# M8830C.net
KiCad netlist of a schematic drawn in EAGLE
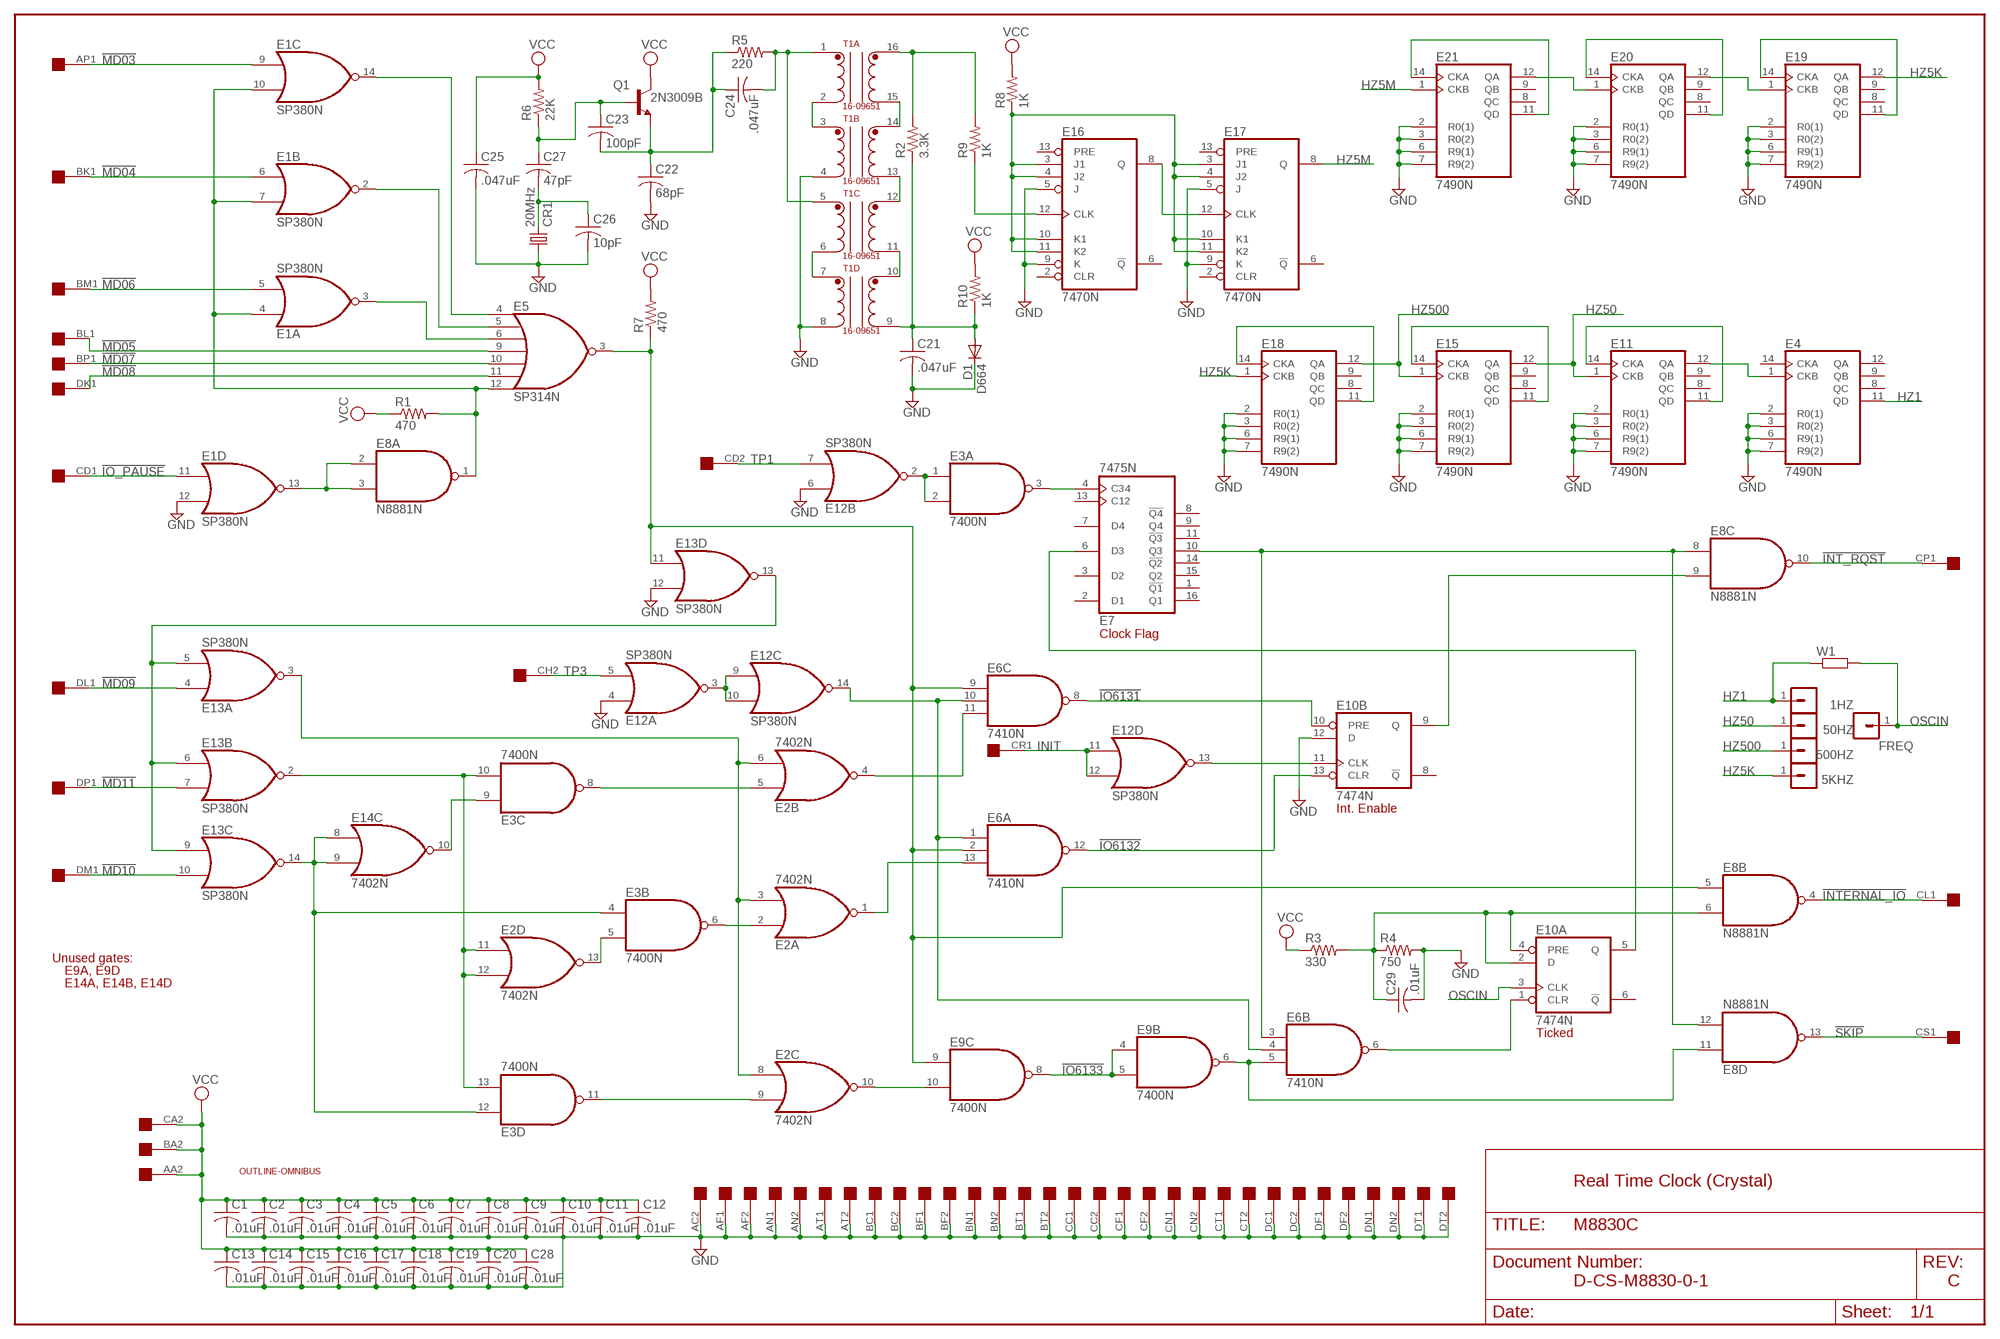
[diagram p0: schematic, sheet 1]

(export (version "E")
  (design (tool "Eeschema 10.0.6"))
  (components
    (comp (ref "1HZ")
      (value "MA01-1")
      (footprint "eagle-import:MA01-1")
      (libsource (lib "eagle-import") (part "MA01-1"))
    )
    (comp (ref "5KHZ")
      (value "MA01-1")
      (footprint "eagle-import:MA01-1")
      (libsource (lib "eagle-import") (part "MA01-1"))
    )
    (comp (ref "50HZ")
      (value "MA01-1")
      (footprint "eagle-import:MA01-1")
      (libsource (lib "eagle-import") (part "MA01-1"))
    )
    (comp (ref "500HZ")
      (value "MA01-1")
      (footprint "eagle-import:MA01-1")
      (libsource (lib "eagle-import") (part "MA01-1"))
    )
    (comp (ref "C1")
      (value ".01uF")
      (footprint "eagle-import:C050-025X075")
      (libsource (lib "eagle-import") (part "C-US050-025X075"))
    )
    (comp (ref "C2")
      (value ".01uF")
      (footprint "eagle-import:C050-025X075")
      (libsource (lib "eagle-import") (part "C-US050-025X075"))
    )
    (comp (ref "C3")
      (value ".01uF")
      (footprint "eagle-import:C050-025X075")
      (libsource (lib "eagle-import") (part "C-US050-025X075"))
    )
    (comp (ref "C4")
      (value ".01uF")
      (footprint "eagle-import:C050-025X075")
      (libsource (lib "eagle-import") (part "C-US050-025X075"))
    )
    (comp (ref "C5")
      (value ".01uF")
      (footprint "eagle-import:C050-025X075")
      (libsource (lib "eagle-import") (part "C-US050-025X075"))
    )
    (comp (ref "C6")
      (value ".01uF")
      (footprint "eagle-import:C050-025X075")
      (libsource (lib "eagle-import") (part "C-US050-025X075"))
    )
    (comp (ref "C7")
      (value ".01uF")
      (footprint "eagle-import:C050-025X075")
      (libsource (lib "eagle-import") (part "C-US050-025X075"))
    )
    (comp (ref "C8")
      (value ".01uF")
      (footprint "eagle-import:C050-025X075")
      (libsource (lib "eagle-import") (part "C-US050-025X075"))
    )
    (comp (ref "C9")
      (value ".01uF")
      (footprint "eagle-import:C050-025X075")
      (libsource (lib "eagle-import") (part "C-US050-025X075"))
    )
    (comp (ref "C10")
      (value ".01uF")
      (footprint "eagle-import:C050-025X075")
      (libsource (lib "eagle-import") (part "C-US050-025X075"))
    )
    (comp (ref "C11")
      (value ".01uF")
      (footprint "eagle-import:C050-025X075")
      (libsource (lib "eagle-import") (part "C-US050-025X075"))
    )
    (comp (ref "C12")
      (value ".01uF")
      (footprint "eagle-import:C050-025X075")
      (libsource (lib "eagle-import") (part "C-US050-025X075"))
    )
    (comp (ref "C13")
      (value ".01uF")
      (footprint "eagle-import:C050-025X075")
      (libsource (lib "eagle-import") (part "C-US050-025X075"))
    )
    (comp (ref "C14")
      (value ".01uF")
      (footprint "eagle-import:C050-025X075")
      (libsource (lib "eagle-import") (part "C-US050-025X075"))
    )
    (comp (ref "C15")
      (value ".01uF")
      (footprint "eagle-import:C050-025X075")
      (libsource (lib "eagle-import") (part "C-US050-025X075"))
    )
    (comp (ref "C16")
      (value ".01uF")
      (footprint "eagle-import:C050-025X075")
      (libsource (lib "eagle-import") (part "C-US050-025X075"))
    )
    (comp (ref "C17")
      (value ".01uF")
      (footprint "eagle-import:C050-025X075")
      (libsource (lib "eagle-import") (part "C-US050-025X075"))
    )
    (comp (ref "C18")
      (value ".01uF")
      (footprint "eagle-import:C050-025X075")
      (libsource (lib "eagle-import") (part "C-US050-025X075"))
    )
    (comp (ref "C19")
      (value ".01uF")
      (footprint "eagle-import:C050-025X075")
      (libsource (lib "eagle-import") (part "C-US050-025X075"))
    )
    (comp (ref "C20")
      (value ".01uF")
      (footprint "eagle-import:C050-025X075")
      (libsource (lib "eagle-import") (part "C-US050-025X075"))
    )
    (comp (ref "C21")
      (value ".047uF")
      (footprint "eagle-import:C050-025X075")
      (libsource (lib "eagle-import") (part "C-US050-025X075"))
    )
    (comp (ref "C22")
      (value "68pF")
      (footprint "eagle-import:C050-025X075")
      (libsource (lib "eagle-import") (part "C-US050-025X075"))
    )
    (comp (ref "C23")
      (value "100pF")
      (footprint "eagle-import:C050-025X075")
      (libsource (lib "eagle-import") (part "C-US050-025X075"))
    )
    (comp (ref "C24")
      (value ".047uF")
      (footprint "eagle-import:C050-025X075")
      (libsource (lib "eagle-import") (part "C-US050-025X075"))
    )
    (comp (ref "C25")
      (value ".047uF")
      (footprint "eagle-import:C050-025X075")
      (libsource (lib "eagle-import") (part "C-US050-025X075"))
    )
    (comp (ref "C26")
      (value "10pF")
      (footprint "eagle-import:C050-025X075")
      (libsource (lib "eagle-import") (part "C-US050-025X075"))
    )
    (comp (ref "C27")
      (value "47pF")
      (footprint "eagle-import:C050-025X075")
      (libsource (lib "eagle-import") (part "C-US050-025X075"))
    )
    (comp (ref "C28")
      (value ".01uF")
      (footprint "eagle-import:C050-025X075")
      (libsource (lib "eagle-import") (part "C-US050-025X075"))
    )
    (comp (ref "C29")
      (value ".01uF")
      (footprint "eagle-import:C050-025X075")
      (libsource (lib "eagle-import") (part "C-US050-025X075"))
    )
    (comp (ref "CR1")
      (value "20MHz")
      (footprint "eagle-import:HC49TL-H")
      (libsource (lib "eagle-import") (part "CRYSTALHC49TL-H"))
    )
    (comp (ref "D1")
      (value "D664")
      (footprint "eagle-import:DO35-10")
      (libsource (lib "eagle-import") (part "DIODE-DO35-10"))
    )
    (comp (ref "E1")
      (value "SP380N")
      (footprint "eagle-import:DIL14")
      (libsource (lib "eagle-import") (part "SP380N"))
    )
    (comp (ref "E2")
      (value "7402N")
      (footprint "eagle-import:DIL14")
      (libsource (lib "eagle-import") (part "7402N"))
    )
    (comp (ref "E3")
      (value "7400N")
      (footprint "eagle-import:DIL14")
      (libsource (lib "eagle-import") (part "7400N"))
    )
    (comp (ref "E4")
      (value "7490N")
      (footprint "eagle-import:DIL14")
      (libsource (lib "eagle-import") (part "7490N"))
    )
    (comp (ref "E5")
      (value "SP314N")
      (footprint "eagle-import:DIL14")
      (libsource (lib "eagle-import") (part "SP314N"))
    )
    (comp (ref "E6")
      (value "7410N")
      (footprint "eagle-import:DIL14")
      (libsource (lib "eagle-import") (part "7410N"))
    )
    (comp (ref "E7")
      (value "7475N")
      (footprint "eagle-import:DIL16")
      (libsource (lib "eagle-import") (part "7475N"))
    )
    (comp (ref "E8")
      (value "N8881N")
      (footprint "eagle-import:DIL14")
      (libsource (lib "eagle-import") (part "N8881N"))
    )
    (comp (ref "E9")
      (value "7400N")
      (footprint "eagle-import:DIL14")
      (libsource (lib "eagle-import") (part "7400N"))
    )
    (comp (ref "E10")
      (value "7474N")
      (footprint "eagle-import:DIL14")
      (libsource (lib "eagle-import") (part "7474NS"))
    )
    (comp (ref "E11")
      (value "7490N")
      (footprint "eagle-import:DIL14")
      (libsource (lib "eagle-import") (part "7490N"))
    )
    (comp (ref "E12")
      (value "SP380N")
      (footprint "eagle-import:DIL14")
      (libsource (lib "eagle-import") (part "SP380N"))
    )
    (comp (ref "E13")
      (value "SP380N")
      (footprint "eagle-import:DIL14")
      (libsource (lib "eagle-import") (part "SP380N"))
    )
    (comp (ref "E14")
      (value "7402N")
      (footprint "eagle-import:DIL14")
      (libsource (lib "eagle-import") (part "7402N"))
    )
    (comp (ref "E15")
      (value "7490N")
      (footprint "eagle-import:DIL14")
      (libsource (lib "eagle-import") (part "7490N"))
    )
    (comp (ref "E16")
      (value "7470N")
      (footprint "eagle-import:DIL14")
      (libsource (lib "eagle-import") (part "7470N"))
    )
    (comp (ref "E17")
      (value "7470N")
      (footprint "eagle-import:DIL14")
      (libsource (lib "eagle-import") (part "7470N"))
    )
    (comp (ref "E18")
      (value "7490N")
      (footprint "eagle-import:DIL14")
      (libsource (lib "eagle-import") (part "7490N"))
    )
    (comp (ref "E19")
      (value "7490N")
      (footprint "eagle-import:DIL14")
      (libsource (lib "eagle-import") (part "7490N"))
    )
    (comp (ref "E20")
      (value "7490N")
      (footprint "eagle-import:DIL14")
      (libsource (lib "eagle-import") (part "7490N"))
    )
    (comp (ref "E21")
      (value "7490N")
      (footprint "eagle-import:DIL14")
      (libsource (lib "eagle-import") (part "7490N"))
    )
    (comp (ref "EDGE")
      (value "QUAD")
      (footprint "eagle-import:EDGE-CON8")
      (libsource (lib "eagle-import") (part "QUAD"))
    )
    (comp (ref "FREQ")
      (value "MA01-1")
      (footprint "eagle-import:MA01-1")
      (libsource (lib "eagle-import") (part "MA01-1"))
    )
    (comp (ref "Q1")
      (value "2N3009B")
      (footprint "eagle-import:TO5")
      (libsource (lib "eagle-import") (part "-NPN-TO5"))
    )
    (comp (ref "R1")
      (value "470")
      (footprint "eagle-import:0207_10")
      (libsource (lib "eagle-import") (part "R-US_0207/10"))
    )
    (comp (ref "R2")
      (value "3.3K")
      (footprint "eagle-import:0207_10")
      (libsource (lib "eagle-import") (part "R-US_0207/10"))
    )
    (comp (ref "R3")
      (value "330")
      (footprint "eagle-import:0207_10")
      (libsource (lib "eagle-import") (part "R-US_0207/10"))
    )
    (comp (ref "R4")
      (value "750")
      (footprint "eagle-import:0207_10")
      (libsource (lib "eagle-import") (part "R-US_0207/10"))
    )
    (comp (ref "R5")
      (value "220")
      (footprint "eagle-import:0207_10")
      (libsource (lib "eagle-import") (part "R-US_0207/10"))
    )
    (comp (ref "R6")
      (value "22K")
      (footprint "eagle-import:0207_10")
      (libsource (lib "eagle-import") (part "R-US_0207/10"))
    )
    (comp (ref "R7")
      (value "470")
      (footprint "eagle-import:0207_10")
      (libsource (lib "eagle-import") (part "R-US_0207/10"))
    )
    (comp (ref "R8")
      (value "1K")
      (footprint "eagle-import:0207_10")
      (libsource (lib "eagle-import") (part "R-US_0207/10"))
    )
    (comp (ref "R9")
      (value "1K")
      (footprint "eagle-import:0207_10")
      (libsource (lib "eagle-import") (part "R-US_0207/10"))
    )
    (comp (ref "R10")
      (value "1K")
      (footprint "eagle-import:0207_10")
      (libsource (lib "eagle-import") (part "R-US_0207/10"))
    )
    (comp (ref "T1")
      (value "16-09651")
      (footprint "eagle-import:DIL16")
      (libsource (lib "eagle-import") (part "16-09651"))
    )
    (comp (ref "U$1")
      (value "OUTLINE-OMNIBUS")
      (footprint "eagle-import:OMNIBUS")
      (libsource (lib "eagle-import") (part "OUTLINE-OMNIBUS"))
    )
    (comp (ref "W1")
      (value "R-EU_0207/10")
      (footprint "eagle-import:0207_10")
      (libsource (lib "eagle-import") (part "R-EU_0207/10"))
    )
  )
  (nets
    (net (code "1") (name "/HZ1") (class "Default")
      (node (ref "1HZ") (pin "1") (pinfunction "1_1") (pintype "passive"))
      (node (ref "E4") (pin "11") (pinfunction "QD_11") (pintype "output"))
      (node (ref "W1") (pin "1") (pinfunction "1_1") (pintype "passive"))
    )
    (net (code "2") (name "/HZ5K") (class "Default")
      (node (ref "5KHZ") (pin "1") (pinfunction "1_1") (pintype "passive"))
      (node (ref "E18") (pin "1") (pinfunction "CKB_1") (pintype "input"))
      (node (ref "E19") (pin "12") (pinfunction "QA_12") (pintype "output"))
    )
    (net (code "3") (name "/HZ5M") (class "Default")
      (node (ref "E17") (pin "8") (pinfunction "Q_8") (pintype "output"))
      (node (ref "E21") (pin "1") (pinfunction "CKB_1") (pintype "input"))
    )
    (net (code "4") (name "/HZ50") (class "Default")
      (node (ref "50HZ") (pin "1") (pinfunction "1_1") (pintype "passive"))
      (node (ref "E11") (pin "1") (pinfunction "CKB_1") (pintype "input"))
      (node (ref "E15") (pin "12") (pinfunction "QA_12") (pintype "output"))
    )
    (net (code "5") (name "/HZ500") (class "Default")
      (node (ref "500HZ") (pin "1") (pinfunction "1_1") (pintype "passive"))
      (node (ref "E15") (pin "1") (pinfunction "CKB_1") (pintype "input"))
      (node (ref "E18") (pin "12") (pinfunction "QA_12") (pintype "output"))
    )
    (net (code "6") (name "/INIT") (class "Default")
      (node (ref "E12") (pin "11") (pinfunction "I0_11") (pintype "input"))
      (node (ref "E12") (pin "12") (pinfunction "I1_12") (pintype "input"))
      (node (ref "EDGE") (pin "CR1") (pinfunction "1_CR1") (pintype "bidirectional"))
    )
    (net (code "7") (name "/OSCIN") (class "Default")
      (node (ref "E10") (pin "3") (pinfunction "CLK_3") (pintype "input"))
      (node (ref "FREQ") (pin "1") (pinfunction "1_1") (pintype "passive"))
      (node (ref "W1") (pin "2") (pinfunction "2_2") (pintype "passive"))
    )
    (net (code "8") (name "/TP1") (class "Default")
      (node (ref "E12") (pin "7") (pinfunction "I1_7") (pintype "input"))
      (node (ref "EDGE") (pin "CD2") (pinfunction "1_CD2") (pintype "bidirectional"))
    )
    (net (code "9") (name "/TP3") (class "Default")
      (node (ref "E12") (pin "5") (pinfunction "I1_5") (pintype "input"))
      (node (ref "EDGE") (pin "CH2") (pinfunction "1_CH2") (pintype "bidirectional"))
    )
    (net (code "10") (name "/~{INTERNAL_IO}") (class "Default")
      (node (ref "E8") (pin "4") (pinfunction "O_4") (pintype "open_collector"))
      (node (ref "EDGE") (pin "CL1") (pinfunction "1_CL1") (pintype "bidirectional"))
    )
    (net (code "11") (name "/~{INT_RQST}") (class "Default")
      (node (ref "E8") (pin "10") (pinfunction "O_10") (pintype "open_collector"))
      (node (ref "EDGE") (pin "CP1") (pinfunction "1_CP1") (pintype "bidirectional"))
    )
    (net (code "12") (name "/~{IO6131}") (class "Default")
      (node (ref "E10") (pin "10") (pinfunction "PRE_10") (pintype "input"))
      (node (ref "E6") (pin "8") (pinfunction "O_8") (pintype "output"))
    )
    (net (code "13") (name "/~{IO6132}") (class "Default")
      (node (ref "E10") (pin "13") (pinfunction "CLR_13") (pintype "input"))
      (node (ref "E6") (pin "12") (pinfunction "O_12") (pintype "output"))
    )
    (net (code "14") (name "/~{IO6133}") (class "Default")
      (node (ref "E9") (pin "4") (pinfunction "I0_4") (pintype "input"))
      (node (ref "E9") (pin "5") (pinfunction "I1_5") (pintype "input"))
      (node (ref "E9") (pin "8") (pinfunction "O_8") (pintype "output"))
    )
    (net (code "15") (name "/~{IO_PAUSE}") (class "Default")
      (node (ref "E1") (pin "11") (pinfunction "I0_11") (pintype "input"))
      (node (ref "EDGE") (pin "CD1") (pinfunction "1_CD1") (pintype "bidirectional"))
    )
    (net (code "16") (name "/~{MD03}") (class "Default")
      (node (ref "E1") (pin "9") (pinfunction "I0_9") (pintype "input"))
      (node (ref "EDGE") (pin "AP1") (pinfunction "1_AP1") (pintype "bidirectional"))
    )
    (net (code "17") (name "/~{MD04}") (class "Default")
      (node (ref "E1") (pin "6") (pinfunction "I0_6") (pintype "input"))
      (node (ref "EDGE") (pin "BK1") (pinfunction "1_BK1") (pintype "bidirectional"))
    )
    (net (code "18") (name "/~{MD05}") (class "Default")
      (node (ref "E5") (pin "9") (pinfunction "I3_9") (pintype "input"))
      (node (ref "EDGE") (pin "BL1") (pinfunction "1_BL1") (pintype "bidirectional"))
    )
    (net (code "19") (name "/~{MD06}") (class "Default")
      (node (ref "E1") (pin "5") (pinfunction "I1_5") (pintype "input"))
      (node (ref "EDGE") (pin "BM1") (pinfunction "1_BM1") (pintype "bidirectional"))
    )
    (net (code "20") (name "/~{MD07}") (class "Default")
      (node (ref "E5") (pin "10") (pinfunction "I4_10") (pintype "input"))
      (node (ref "EDGE") (pin "BP1") (pinfunction "1_BP1") (pintype "bidirectional"))
    )
    (net (code "21") (name "/~{MD08}") (class "Default")
      (node (ref "E5") (pin "11") (pinfunction "I5_11") (pintype "input"))
      (node (ref "EDGE") (pin "DK1") (pinfunction "1_DK1") (pintype "bidirectional"))
    )
    (net (code "22") (name "/~{MD09}") (class "Default")
      (node (ref "E13") (pin "4") (pinfunction "I0_4") (pintype "input"))
      (node (ref "EDGE") (pin "DL1") (pinfunction "1_DL1") (pintype "bidirectional"))
    )
    (net (code "23") (name "/~{MD10}") (class "Default")
      (node (ref "E13") (pin "10") (pinfunction "I1_10") (pintype "input"))
      (node (ref "EDGE") (pin "DM1") (pinfunction "1_DM1") (pintype "bidirectional"))
    )
    (net (code "24") (name "/~{MD11}") (class "Default")
      (node (ref "E13") (pin "7") (pinfunction "I1_7") (pintype "input"))
      (node (ref "EDGE") (pin "DP1") (pinfunction "1_DP1") (pintype "bidirectional"))
    )
    (net (code "25") (name "/~{SKIP}") (class "Default")
      (node (ref "E8") (pin "13") (pinfunction "O_13") (pintype "open_collector"))
      (node (ref "EDGE") (pin "CS1") (pinfunction "1_CS1") (pintype "bidirectional"))
    )
    (net (code "26") (name "GND") (class "Default")
      (node (ref "C1") (pin "2") (pinfunction "2_2") (pintype "passive"))
      (node (ref "C10") (pin "2") (pinfunction "2_2") (pintype "passive"))
      (node (ref "C11") (pin "2") (pinfunction "2_2") (pintype "passive"))
      (node (ref "C12") (pin "2") (pinfunction "2_2") (pintype "passive"))
      (node (ref "C13") (pin "2") (pinfunction "2_2") (pintype "passive"))
      (node (ref "C14") (pin "2") (pinfunction "2_2") (pintype "passive"))
      (node (ref "C15") (pin "2") (pinfunction "2_2") (pintype "passive"))
      (node (ref "C16") (pin "2") (pinfunction "2_2") (pintype "passive"))
      (node (ref "C17") (pin "2") (pinfunction "2_2") (pintype "passive"))
      (node (ref "C18") (pin "2") (pinfunction "2_2") (pintype "passive"))
      (node (ref "C19") (pin "2") (pinfunction "2_2") (pintype "passive"))
      (node (ref "C2") (pin "2") (pinfunction "2_2") (pintype "passive"))
      (node (ref "C20") (pin "2") (pinfunction "2_2") (pintype "passive"))
      (node (ref "C21") (pin "2") (pinfunction "2_2") (pintype "passive"))
      (node (ref "C22") (pin "2") (pinfunction "2_2") (pintype "passive"))
      (node (ref "C25") (pin "2") (pinfunction "2_2") (pintype "passive"))
      (node (ref "C26") (pin "2") (pinfunction "2_2") (pintype "passive"))
      (node (ref "C28") (pin "2") (pinfunction "2_2") (pintype "passive"))
      (node (ref "C29") (pin "2") (pinfunction "2_2") (pintype "passive"))
      (node (ref "C3") (pin "2") (pinfunction "2_2") (pintype "passive"))
      (node (ref "C4") (pin "2") (pinfunction "2_2") (pintype "passive"))
      (node (ref "C5") (pin "2") (pinfunction "2_2") (pintype "passive"))
      (node (ref "C6") (pin "2") (pinfunction "2_2") (pintype "passive"))
      (node (ref "C7") (pin "2") (pinfunction "2_2") (pintype "passive"))
      (node (ref "C8") (pin "2") (pinfunction "2_2") (pintype "passive"))
      (node (ref "C9") (pin "2") (pinfunction "2_2") (pintype "passive"))
      (node (ref "CR1") (pin "1") (pinfunction "1_1") (pintype "passive"))
      (node (ref "D1") (pin "C") (pinfunction "C_C") (pintype "passive"))
      (node (ref "E1") (pin "12") (pinfunction "I1_12") (pintype "input"))
      (node (ref "E10") (pin "12") (pinfunction "D_12") (pintype "input"))
      (node (ref "E11") (pin "2") (pinfunction "R0(1)_2") (pintype "input"))
      (node (ref "E11") (pin "3") (pinfunction "R0(2)_3") (pintype "input"))
      (node (ref "E11") (pin "6") (pinfunction "R9(1)_6") (pintype "input"))
      (node (ref "E11") (pin "7") (pinfunction "R9(2)_7") (pintype "input"))
      (node (ref "E12") (pin "4") (pinfunction "I0_4") (pintype "input"))
      (node (ref "E12") (pin "6") (pinfunction "I0_6") (pintype "input"))
      (node (ref "E13") (pin "12") (pinfunction "I1_12") (pintype "input"))
      (node (ref "E15") (pin "2") (pinfunction "R0(1)_2") (pintype "input"))
      (node (ref "E15") (pin "3") (pinfunction "R0(2)_3") (pintype "input"))
      (node (ref "E15") (pin "6") (pinfunction "R9(1)_6") (pintype "input"))
      (node (ref "E15") (pin "7") (pinfunction "R9(2)_7") (pintype "input"))
      (node (ref "E16") (pin "5") (pinfunction "J_5") (pintype "input"))
      (node (ref "E16") (pin "9") (pinfunction "K_9") (pintype "input"))
      (node (ref "E17") (pin "5") (pinfunction "J_5") (pintype "input"))
      (node (ref "E17") (pin "9") (pinfunction "K_9") (pintype "input"))
      (node (ref "E18") (pin "2") (pinfunction "R0(1)_2") (pintype "input"))
      (node (ref "E18") (pin "3") (pinfunction "R0(2)_3") (pintype "input"))
      (node (ref "E18") (pin "6") (pinfunction "R9(1)_6") (pintype "input"))
      (node (ref "E18") (pin "7") (pinfunction "R9(2)_7") (pintype "input"))
      (node (ref "E19") (pin "2") (pinfunction "R0(1)_2") (pintype "input"))
      (node (ref "E19") (pin "3") (pinfunction "R0(2)_3") (pintype "input"))
      (node (ref "E19") (pin "6") (pinfunction "R9(1)_6") (pintype "input"))
      (node (ref "E19") (pin "7") (pinfunction "R9(2)_7") (pintype "input"))
      (node (ref "E20") (pin "2") (pinfunction "R0(1)_2") (pintype "input"))
      (node (ref "E20") (pin "3") (pinfunction "R0(2)_3") (pintype "input"))
      (node (ref "E20") (pin "6") (pinfunction "R9(1)_6") (pintype "input"))
      (node (ref "E20") (pin "7") (pinfunction "R9(2)_7") (pintype "input"))
      (node (ref "E21") (pin "2") (pinfunction "R0(1)_2") (pintype "input"))
      (node (ref "E21") (pin "3") (pinfunction "R0(2)_3") (pintype "input"))
      (node (ref "E21") (pin "6") (pinfunction "R9(1)_6") (pintype "input"))
      (node (ref "E21") (pin "7") (pinfunction "R9(2)_7") (pintype "input"))
      (node (ref "E4") (pin "2") (pinfunction "R0(1)_2") (pintype "input"))
      (node (ref "E4") (pin "3") (pinfunction "R0(2)_3") (pintype "input"))
      (node (ref "E4") (pin "6") (pinfunction "R9(1)_6") (pintype "input"))
      (node (ref "E4") (pin "7") (pinfunction "R9(2)_7") (pintype "input"))
      (node (ref "EDGE") (pin "AC2") (pinfunction "1_AC2") (pintype "bidirectional"))
      (node (ref "EDGE") (pin "AF1") (pinfunction "1_AF1") (pintype "bidirectional"))
      (node (ref "EDGE") (pin "AF2") (pinfunction "1_AF2") (pintype "bidirectional"))
      (node (ref "EDGE") (pin "AN1") (pinfunction "1_AN1") (pintype "bidirectional"))
      (node (ref "EDGE") (pin "AN2") (pinfunction "1_AN2") (pintype "bidirectional"))
      (node (ref "EDGE") (pin "AT1") (pinfunction "1_AT1") (pintype "bidirectional"))
      (node (ref "EDGE") (pin "AT2") (pinfunction "1_AT2") (pintype "bidirectional"))
      (node (ref "EDGE") (pin "BC1") (pinfunction "1_BC1") (pintype "bidirectional"))
      (node (ref "EDGE") (pin "BC2") (pinfunction "1_BC2") (pintype "bidirectional"))
      (node (ref "EDGE") (pin "BF1") (pinfunction "1_BF1") (pintype "bidirectional"))
      (node (ref "EDGE") (pin "BF2") (pinfunction "1_BF2") (pintype "bidirectional"))
      (node (ref "EDGE") (pin "BN1") (pinfunction "1_BN1") (pintype "bidirectional"))
      (node (ref "EDGE") (pin "BN2") (pinfunction "1_BN2") (pintype "bidirectional"))
      (node (ref "EDGE") (pin "BT1") (pinfunction "1_BT1") (pintype "bidirectional"))
      (node (ref "EDGE") (pin "BT2") (pinfunction "1_BT2") (pintype "bidirectional"))
      (node (ref "EDGE") (pin "CC1") (pinfunction "1_CC1") (pintype "bidirectional"))
      (node (ref "EDGE") (pin "CC2") (pinfunction "1_CC2") (pintype "bidirectional"))
      (node (ref "EDGE") (pin "CF1") (pinfunction "1_CF1") (pintype "bidirectional"))
      (node (ref "EDGE") (pin "CF2") (pinfunction "1_CF2") (pintype "bidirectional"))
      (node (ref "EDGE") (pin "CN1") (pinfunction "1_CN1") (pintype "bidirectional"))
      (node (ref "EDGE") (pin "CN2") (pinfunction "1_CN2") (pintype "bidirectional"))
      (node (ref "EDGE") (pin "CT1") (pinfunction "1_CT1") (pintype "bidirectional"))
      (node (ref "EDGE") (pin "CT2") (pinfunction "1_CT2") (pintype "bidirectional"))
      (node (ref "EDGE") (pin "DC1") (pinfunction "1_DC1") (pintype "bidirectional"))
      (node (ref "EDGE") (pin "DC2") (pinfunction "1_DC2") (pintype "bidirectional"))
      (node (ref "EDGE") (pin "DF1") (pinfunction "1_DF1") (pintype "bidirectional"))
      (node (ref "EDGE") (pin "DF2") (pinfunction "1_DF2") (pintype "bidirectional"))
      (node (ref "EDGE") (pin "DN1") (pinfunction "1_DN1") (pintype "bidirectional"))
      (node (ref "EDGE") (pin "DN2") (pinfunction "1_DN2") (pintype "bidirectional"))
      (node (ref "EDGE") (pin "DT1") (pinfunction "1_DT1") (pintype "bidirectional"))
      (node (ref "EDGE") (pin "DT2") (pinfunction "1_DT2") (pintype "bidirectional"))
      (node (ref "R4") (pin "2") (pinfunction "2_2") (pintype "passive"))
      (node (ref "T1") (pin "4") (pinfunction "P$7_4") (pintype "passive"))
      (node (ref "T1") (pin "8") (pinfunction "P$7_8") (pintype "passive"))
    )
    (net (code "27") (name "Net-(C26-Pad1)") (class "Default")
      (node (ref "C26") (pin "1") (pinfunction "1_1") (pintype "passive"))
      (node (ref "C27") (pin "2") (pinfunction "2_2") (pintype "passive"))
      (node (ref "CR1") (pin "2") (pinfunction "2_2") (pintype "passive"))
    )
    (net (code "28") (name "Net-(E1A-I0)") (class "Default")
      (node (ref "E1") (pin "10") (pinfunction "I1_10") (pintype "input"))
      (node (ref "E1") (pin "4") (pinfunction "I0_4") (pintype "input"))
      (node (ref "E1") (pin "7") (pinfunction "I1_7") (pintype "input"))
      (node (ref "E5") (pin "12") (pinfunction "I6_12") (pintype "input"))
      (node (ref "E8") (pin "1") (pinfunction "O_1") (pintype "open_collector"))
      (node (ref "R1") (pin "2") (pinfunction "2_2") (pintype "passive"))
    )
    (net (code "29") (name "Net-(E1A-O)") (class "Default")
      (node (ref "E1") (pin "3") (pinfunction "O_3") (pintype "output"))
      (node (ref "E5") (pin "6") (pinfunction "I2_6") (pintype "input"))
    )
    (net (code "30") (name "Net-(E1B-O)") (class "Default")
      (node (ref "E1") (pin "2") (pinfunction "O_2") (pintype "output"))
      (node (ref "E5") (pin "5") (pinfunction "I1_5") (pintype "input"))
    )
    (net (code "31") (name "Net-(E1C-O)") (class "Default")
      (node (ref "E1") (pin "14") (pinfunction "O_14") (pintype "output"))
      (node (ref "E5") (pin "4") (pinfunction "I0_4") (pintype "input"))
    )
    (net (code "32") (name "Net-(E1D-O)") (class "Default")
      (node (ref "E1") (pin "13") (pinfunction "O_13") (pintype "output"))
      (node (ref "E8") (pin "2") (pinfunction "I0_2") (pintype "input"))
      (node (ref "E8") (pin "3") (pinfunction "I1_3") (pintype "input"))
    )
    (net (code "33") (name "Net-(E2A-I0)") (class "Default")
      (node (ref "E2") (pin "2") (pinfunction "I0_2") (pintype "input"))
      (node (ref "E3") (pin "6") (pinfunction "O_6") (pintype "output"))
    )
    (net (code "34") (name "Net-(E2A-O)") (class "Default")
      (node (ref "E2") (pin "1") (pinfunction "O_1") (pintype "output"))
      (node (ref "E6") (pin "13") (pinfunction "I2_13") (pintype "input"))
    )
    (net (code "35") (name "Net-(E2B-I0)") (class "Default")
      (node (ref "E2") (pin "5") (pinfunction "I0_5") (pintype "input"))
      (node (ref "E3") (pin "8") (pinfunction "O_8") (pintype "output"))
    )
    (net (code "36") (name "Net-(E2B-O)") (class "Default")
      (node (ref "E2") (pin "4") (pinfunction "O_4") (pintype "output"))
      (node (ref "E6") (pin "11") (pinfunction "I2_11") (pintype "input"))
    )
    (net (code "37") (name "Net-(E2C-I1)") (class "Default")
      (node (ref "E2") (pin "9") (pinfunction "I1_9") (pintype "input"))
      (node (ref "E3") (pin "11") (pinfunction "O_11") (pintype "output"))
    )
    (net (code "38") (name "Net-(E2C-O)") (class "Default")
      (node (ref "E2") (pin "10") (pinfunction "O_10") (pintype "output"))
      (node (ref "E9") (pin "10") (pinfunction "I1_10") (pintype "input"))
    )
    (net (code "39") (name "Net-(E2D-O)") (class "Default")
      (node (ref "E2") (pin "13") (pinfunction "O_13") (pintype "output"))
      (node (ref "E3") (pin "5") (pinfunction "I1_5") (pintype "input"))
    )
    (net (code "40") (name "Net-(E3A-O)") (class "Default")
      (node (ref "E3") (pin "3") (pinfunction "O_3") (pintype "output"))
      (node (ref "E7") (pin "4") (pinfunction "C34_4") (pintype "input"))
    )
    (net (code "41") (name "Net-(E6B-I0)") (class "Default")
      (node (ref "E6") (pin "3") (pinfunction "I0_3") (pintype "input"))
      (node (ref "E7") (pin "10") (pinfunction "Q3_10") (pintype "output"))
      (node (ref "E8") (pin "12") (pinfunction "I1_12") (pintype "input"))
      (node (ref "E8") (pin "8") (pinfunction "I0_8") (pintype "input"))
    )
    (net (code "42") (name "Net-(E6B-I2)") (class "Default")
      (node (ref "E6") (pin "5") (pinfunction "I2_5") (pintype "input"))
      (node (ref "E8") (pin "11") (pinfunction "I0_11") (pintype "input"))
      (node (ref "E9") (pin "6") (pinfunction "O_6") (pintype "output"))
    )
    (net (code "43") (name "Net-(E10A-CLR)") (class "Default")
      (node (ref "E10") (pin "1") (pinfunction "CLR_1") (pintype "input"))
      (node (ref "E6") (pin "6") (pinfunction "O_6") (pintype "output"))
    )
    (net (code "44") (name "Net-(E10A-D)") (class "Default")
      (node (ref "C29") (pin "1") (pinfunction "1_1") (pintype "passive"))
      (node (ref "E10") (pin "2") (pinfunction "D_2") (pintype "input"))
      (node (ref "E10") (pin "4") (pinfunction "PRE_4") (pintype "input"))
      (node (ref "E8") (pin "6") (pinfunction "I1_6") (pintype "input"))
      (node (ref "R3") (pin "2") (pinfunction "2_2") (pintype "passive"))
      (node (ref "R4") (pin "1") (pinfunction "1_1") (pintype "passive"))
    )
    (net (code "45") (name "Net-(E10A-Q)") (class "Default")
      (node (ref "E10") (pin "5") (pinfunction "Q_5") (pintype "output"))
      (node (ref "E7") (pin "6") (pinfunction "D3_6") (pintype "input"))
    )
    (net (code "46") (name "Net-(E10B-CLK)") (class "Default")
      (node (ref "E10") (pin "11") (pinfunction "CLK_11") (pintype "input"))
      (node (ref "E12") (pin "13") (pinfunction "O_13") (pintype "output"))
    )
    (net (code "47") (name "Net-(E10B-Q)") (class "Default")
      (node (ref "E10") (pin "9") (pinfunction "Q_9") (pintype "output"))
      (node (ref "E8") (pin "9") (pinfunction "I1_9") (pintype "input"))
    )
    (net (code "48") (name "Net-(E11A-CKA)") (class "Default")
      (node (ref "E11") (pin "11") (pinfunction "QD_11") (pintype "output"))
      (node (ref "E11") (pin "14") (pinfunction "CKA_14") (pintype "input"))
    )
    (net (code "49") (name "Net-(E11A-QA)") (class "Default")
      (node (ref "E11") (pin "12") (pinfunction "QA_12") (pintype "output"))
      (node (ref "E4") (pin "1") (pinfunction "CKB_1") (pintype "input"))
    )
    (net (code "50") (name "Net-(E12A-O)") (class "Default")
      (node (ref "E12") (pin "10") (pinfunction "I1_10") (pintype "input"))
      (node (ref "E12") (pin "3") (pinfunction "O_3") (pintype "output"))
      (node (ref "E12") (pin "9") (pinfunction "I0_9") (pintype "input"))
    )
    (net (code "51") (name "Net-(E12B-O)") (class "Default")
      (node (ref "E12") (pin "2") (pinfunction "O_2") (pintype "output"))
      (node (ref "E3") (pin "1") (pinfunction "I0_1") (pintype "input"))
      (node (ref "E3") (pin "2") (pinfunction "I1_2") (pintype "input"))
    )
    (net (code "52") (name "Net-(E12C-O)") (class "Default")
      (node (ref "E12") (pin "14") (pinfunction "O_14") (pintype "output"))
      (node (ref "E6") (pin "1") (pinfunction "I0_1") (pintype "input"))
      (node (ref "E6") (pin "10") (pinfunction "I1_10") (pintype "input"))
      (node (ref "E6") (pin "4") (pinfunction "I1_4") (pintype "input"))
    )
    (net (code "53") (name "Net-(E13A-I1)") (class "Default")
      (node (ref "E13") (pin "13") (pinfunction "O_13") (pintype "output"))
      (node (ref "E13") (pin "5") (pinfunction "I1_5") (pintype "input"))
      (node (ref "E13") (pin "6") (pinfunction "I0_6") (pintype "input"))
      (node (ref "E13") (pin "9") (pinfunction "I0_9") (pintype "input"))
    )
    (net (code "54") (name "Net-(E13A-O)") (class "Default")
      (node (ref "E13") (pin "3") (pinfunction "O_3") (pintype "output"))
      (node (ref "E2") (pin "3") (pinfunction "I1_3") (pintype "input"))
      (node (ref "E2") (pin "6") (pinfunction "I1_6") (pintype "input"))
      (node (ref "E2") (pin "8") (pinfunction "I0_8") (pintype "input"))
    )
    (net (code "55") (name "Net-(E13B-O)") (class "Default")
      (node (ref "E13") (pin "2") (pinfunction "O_2") (pintype "output"))
      (node (ref "E2") (pin "11") (pinfunction "I0_11") (pintype "input"))
      (node (ref "E2") (pin "12") (pinfunction "I1_12") (pintype "input"))
      (node (ref "E3") (pin "10") (pinfunction "I1_10") (pintype "input"))
      (node (ref "E3") (pin "13") (pinfunction "I1_13") (pintype "input"))
    )
    (net (code "56") (name "Net-(E13C-O)") (class "Default")
      (node (ref "E13") (pin "14") (pinfunction "O_14") (pintype "output"))
      (node (ref "E14") (pin "8") (pinfunction "I0_8") (pintype "input"))
      (node (ref "E14") (pin "9") (pinfunction "I1_9") (pintype "input"))
      (node (ref "E3") (pin "12") (pinfunction "I0_12") (pintype "input"))
      (node (ref "E3") (pin "4") (pinfunction "I0_4") (pintype "input"))
    )
    (net (code "57") (name "Net-(E13D-I0)") (class "Default")
      (node (ref "E13") (pin "11") (pinfunction "I0_11") (pintype "input"))
      (node (ref "E5") (pin "3") (pinfunction "O_3") (pintype "output"))
      (node (ref "E6") (pin "2") (pinfunction "I1_2") (pintype "input"))
      (node (ref "E6") (pin "9") (pinfunction "I0_9") (pintype "input"))
      (node (ref "E8") (pin "5") (pinfunction "I0_5") (pintype "input"))
      (node (ref "E9") (pin "9") (pinfunction "I0_9") (pintype "input"))
      (node (ref "R7") (pin "1") (pinfunction "1_1") (pintype "passive"))
    )
    (net (code "58") (name "Net-(E14C-O)") (class "Default")
      (node (ref "E14") (pin "10") (pinfunction "O_10") (pintype "output"))
      (node (ref "E3") (pin "9") (pinfunction "I0_9") (pintype "input"))
    )
    (net (code "59") (name "Net-(E15A-CKA)") (class "Default")
      (node (ref "E15") (pin "11") (pinfunction "QD_11") (pintype "output"))
      (node (ref "E15") (pin "14") (pinfunction "CKA_14") (pintype "input"))
    )
    (net (code "60") (name "Net-(E16A-CLK)") (class "Default")
      (node (ref "E16") (pin "12") (pinfunction "CLK_12") (pintype "input"))
      (node (ref "R9") (pin "1") (pinfunction "1_1") (pintype "passive"))
    )
    (net (code "61") (name "Net-(E16A-J1)") (class "Default")
      (node (ref "E16") (pin "10") (pinfunction "K1_10") (pintype "input"))
      (node (ref "E16") (pin "11") (pinfunction "K2_11") (pintype "input"))
      (node (ref "E16") (pin "3") (pinfunction "J1_3") (pintype "input"))
      (node (ref "E16") (pin "4") (pinfunction "J2_4") (pintype "input"))
      (node (ref "E17") (pin "10") (pinfunction "K1_10") (pintype "input"))
      (node (ref "E17") (pin "11") (pinfunction "K2_11") (pintype "input"))
      (node (ref "E17") (pin "3") (pinfunction "J1_3") (pintype "input"))
      (node (ref "E17") (pin "4") (pinfunction "J2_4") (pintype "input"))
      (node (ref "R8") (pin "1") (pinfunction "1_1") (pintype "passive"))
    )
    (net (code "62") (name "Net-(E16A-Q)") (class "Default")
      (node (ref "E16") (pin "8") (pinfunction "Q_8") (pintype "output"))
      (node (ref "E17") (pin "12") (pinfunction "CLK_12") (pintype "input"))
    )
    (net (code "63") (name "Net-(E18A-CKA)") (class "Default")
      (node (ref "E18") (pin "11") (pinfunction "QD_11") (pintype "output"))
      (node (ref "E18") (pin "14") (pinfunction "CKA_14") (pintype "input"))
    )
    (net (code "64") (name "Net-(E19A-CKA)") (class "Default")
      (node (ref "E19") (pin "11") (pinfunction "QD_11") (pintype "output"))
      (node (ref "E19") (pin "14") (pinfunction "CKA_14") (pintype "input"))
    )
    (net (code "65") (name "Net-(E19A-CKB)") (class "Default")
      (node (ref "E19") (pin "1") (pinfunction "CKB_1") (pintype "input"))
      (node (ref "E20") (pin "12") (pinfunction "QA_12") (pintype "output"))
    )
    (net (code "66") (name "Net-(E20A-CKA)") (class "Default")
      (node (ref "E20") (pin "11") (pinfunction "QD_11") (pintype "output"))
      (node (ref "E20") (pin "14") (pinfunction "CKA_14") (pintype "input"))
    )
    (net (code "67") (name "Net-(E20A-CKB)") (class "Default")
      (node (ref "E20") (pin "1") (pinfunction "CKB_1") (pintype "input"))
      (node (ref "E21") (pin "12") (pinfunction "QA_12") (pintype "output"))
    )
    (net (code "68") (name "Net-(E21A-CKA)") (class "Default")
      (node (ref "E21") (pin "11") (pinfunction "QD_11") (pintype "output"))
      (node (ref "E21") (pin "14") (pinfunction "CKA_14") (pintype "input"))
    )
    (net (code "69") (name "Net-(Q1-B)") (class "Default")
      (node (ref "C23") (pin "1") (pinfunction "1_1") (pintype "passive"))
      (node (ref "C27") (pin "1") (pinfunction "1_1") (pintype "passive"))
      (node (ref "Q1") (pin "2") (pinfunction "B_2") (pintype "passive"))
      (node (ref "R6") (pin "1") (pinfunction "1_1") (pintype "passive"))
    )
    (net (code "70") (name "Net-(Q1-E)") (class "Default")
      (node (ref "C22") (pin "1") (pinfunction "1_1") (pintype "passive"))
      (node (ref "C23") (pin "2") (pinfunction "2_2") (pintype "passive"))
      (node (ref "C24") (pin "1") (pinfunction "1_1") (pintype "passive"))
      (node (ref "Q1") (pin "1") (pinfunction "E_1") (pintype "passive"))
      (node (ref "R5") (pin "1") (pinfunction "1_1") (pintype "passive"))
    )
    (net (code "71") (name "Net-(T1A-P$2)") (class "Default")
      (node (ref "C24") (pin "2") (pinfunction "2_2") (pintype "passive"))
      (node (ref "R5") (pin "2") (pinfunction "2_2") (pintype "passive"))
      (node (ref "T1") (pin "1") (pinfunction "P$2_1") (pintype "passive"))
      (node (ref "T1") (pin "5") (pinfunction "P$2_5") (pintype "passive"))
    )
    (net (code "72") (name "Net-(T1A-P$4)") (class "Default")
      (node (ref "R2") (pin "2") (pinfunction "2_2") (pintype "passive"))
      (node (ref "R9") (pin "2") (pinfunction "2_2") (pintype "passive"))
      (node (ref "T1") (pin "16") (pinfunction "P$4_16") (pintype "passive"))
    )
    (net (code "73") (name "Net-(T1A-P$5)") (class "Default")
      (node (ref "T1") (pin "14") (pinfunction "P$4_14") (pintype "passive"))
      (node (ref "T1") (pin "15") (pinfunction "P$5_15") (pintype "passive"))
    )
    (net (code "74") (name "Net-(T1A-P$7)") (class "Default")
      (node (ref "T1") (pin "2") (pinfunction "P$7_2") (pintype "passive"))
      (node (ref "T1") (pin "3") (pinfunction "P$2_3") (pintype "passive"))
    )
    (net (code "75") (name "Net-(T1B-P$5)") (class "Default")
      (node (ref "T1") (pin "12") (pinfunction "P$4_12") (pintype "passive"))
      (node (ref "T1") (pin "13") (pinfunction "P$5_13") (pintype "passive"))
    )
    (net (code "76") (name "Net-(T1C-P$5)") (class "Default")
      (node (ref "T1") (pin "10") (pinfunction "P$4_10") (pintype "passive"))
      (node (ref "T1") (pin "11") (pinfunction "P$5_11") (pintype "passive"))
    )
    (net (code "77") (name "Net-(T1C-P$7)") (class "Default")
      (node (ref "T1") (pin "6") (pinfunction "P$7_6") (pintype "passive"))
      (node (ref "T1") (pin "7") (pinfunction "P$2_7") (pintype "passive"))
    )
    (net (code "78") (name "Net-(T1D-P$5)") (class "Default")
      (node (ref "C21") (pin "1") (pinfunction "1_1") (pintype "passive"))
      (node (ref "D1") (pin "A") (pinfunction "A_A") (pintype "passive"))
      (node (ref "R10") (pin "1") (pinfunction "1_1") (pintype "passive"))
      (node (ref "R2") (pin "1") (pinfunction "1_1") (pintype "passive"))
      (node (ref "T1") (pin "9") (pinfunction "P$5_9") (pintype "passive"))
    )
    (net (code "79") (name "VCC") (class "Default")
      (node (ref "C1") (pin "1") (pinfunction "1_1") (pintype "passive"))
      (node (ref "C10") (pin "1") (pinfunction "1_1") (pintype "passive"))
      (node (ref "C11") (pin "1") (pinfunction "1_1") (pintype "passive"))
      (node (ref "C12") (pin "1") (pinfunction "1_1") (pintype "passive"))
      (node (ref "C13") (pin "1") (pinfunction "1_1") (pintype "passive"))
      (node (ref "C14") (pin "1") (pinfunction "1_1") (pintype "passive"))
      (node (ref "C15") (pin "1") (pinfunction "1_1") (pintype "passive"))
      (node (ref "C16") (pin "1") (pinfunction "1_1") (pintype "passive"))
      (node (ref "C17") (pin "1") (pinfunction "1_1") (pintype "passive"))
      (node (ref "C18") (pin "1") (pinfunction "1_1") (pintype "passive"))
      (node (ref "C19") (pin "1") (pinfunction "1_1") (pintype "passive"))
      (node (ref "C2") (pin "1") (pinfunction "1_1") (pintype "passive"))
      (node (ref "C20") (pin "1") (pinfunction "1_1") (pintype "passive"))
      (node (ref "C25") (pin "1") (pinfunction "1_1") (pintype "passive"))
      (node (ref "C28") (pin "1") (pinfunction "1_1") (pintype "passive"))
      (node (ref "C3") (pin "1") (pinfunction "1_1") (pintype "passive"))
      (node (ref "C4") (pin "1") (pinfunction "1_1") (pintype "passive"))
      (node (ref "C5") (pin "1") (pinfunction "1_1") (pintype "passive"))
      (node (ref "C6") (pin "1") (pinfunction "1_1") (pintype "passive"))
      (node (ref "C7") (pin "1") (pinfunction "1_1") (pintype "passive"))
      (node (ref "C8") (pin "1") (pinfunction "1_1") (pintype "passive"))
      (node (ref "C9") (pin "1") (pinfunction "1_1") (pintype "passive"))
      (node (ref "EDGE") (pin "AA2") (pinfunction "1_AA2") (pintype "bidirectional"))
      (node (ref "EDGE") (pin "BA2") (pinfunction "1_BA2") (pintype "bidirectional"))
      (node (ref "EDGE") (pin "CA2") (pinfunction "1_CA2") (pintype "bidirectional"))
      (node (ref "Q1") (pin "3") (pinfunction "C_3") (pintype "passive"))
      (node (ref "R1") (pin "1") (pinfunction "1_1") (pintype "passive"))
      (node (ref "R10") (pin "2") (pinfunction "2_2") (pintype "passive"))
      (node (ref "R3") (pin "1") (pinfunction "1_1") (pintype "passive"))
      (node (ref "R6") (pin "2") (pinfunction "2_2") (pintype "passive"))
      (node (ref "R7") (pin "2") (pinfunction "2_2") (pintype "passive"))
      (node (ref "R8") (pin "2") (pinfunction "2_2") (pintype "passive"))
    )
    (net (code "80") (name "unconnected-(E4A-CKA-Pad14)") (class "Default")
      (node (ref "E4") (pin "14") (pinfunction "CKA_14") (pintype "input"))
    )
    (net (code "81") (name "unconnected-(E4A-QA-Pad12)") (class "Default")
      (node (ref "E4") (pin "12") (pinfunction "QA_12") (pintype "output"))
    )
    (net (code "82") (name "unconnected-(E4A-QB-Pad9)") (class "Default")
      (node (ref "E4") (pin "9") (pinfunction "QB_9") (pintype "output"))
    )
    (net (code "83") (name "unconnected-(E4A-QC-Pad8)") (class "Default")
      (node (ref "E4") (pin "8") (pinfunction "QC_8") (pintype "output"))
    )
    (net (code "84") (name "unconnected-(E7A-C12-Pad13)") (class "Default")
      (node (ref "E7") (pin "13") (pinfunction "C12_13") (pintype "input"))
    )
    (net (code "85") (name "unconnected-(E7A-D1-Pad2)") (class "Default")
      (node (ref "E7") (pin "2") (pinfunction "D1_2") (pintype "input"))
    )
    (net (code "86") (name "unconnected-(E7A-D2-Pad3)") (class "Default")
      (node (ref "E7") (pin "3") (pinfunction "D2_3") (pintype "input"))
    )
    (net (code "87") (name "unconnected-(E7A-D4-Pad7)") (class "Default")
      (node (ref "E7") (pin "7") (pinfunction "D4_7") (pintype "input"))
    )
    (net (code "88") (name "unconnected-(E7A-Q1-Pad16)") (class "Default")
      (node (ref "E7") (pin "16") (pinfunction "Q1_16") (pintype "output"))
    )
    (net (code "89") (name "unconnected-(E7A-Q2-Pad15)") (class "Default")
      (node (ref "E7") (pin "15") (pinfunction "Q2_15") (pintype "output"))
    )
    (net (code "90") (name "unconnected-(E7A-Q4-Pad9)") (class "Default")
      (node (ref "E7") (pin "9") (pinfunction "Q4_9") (pintype "output"))
    )
    (net (code "91") (name "unconnected-(E7A-~{Q1}-Pad1)") (class "Default")
      (node (ref "E7") (pin "1") (pinfunction "~{Q1}_1") (pintype "output"))
    )
    (net (code "92") (name "unconnected-(E7A-~{Q2}-Pad14)") (class "Default")
      (node (ref "E7") (pin "14") (pinfunction "~{Q2}_14") (pintype "output"))
    )
    (net (code "93") (name "unconnected-(E7A-~{Q3}-Pad11)") (class "Default")
      (node (ref "E7") (pin "11") (pinfunction "~{Q3}_11") (pintype "output"))
    )
    (net (code "94") (name "unconnected-(E7A-~{Q4}-Pad8)") (class "Default")
      (node (ref "E7") (pin "8") (pinfunction "~{Q4}_8") (pintype "output"))
    )
    (net (code "95") (name "unconnected-(E10A-~{Q}-Pad6)") (class "Default")
      (node (ref "E10") (pin "6") (pinfunction "~{Q}_6") (pintype "output"))
    )
    (net (code "96") (name "unconnected-(E10B-~{Q}-Pad8)") (class "Default")
      (node (ref "E10") (pin "8") (pinfunction "~{Q}_8") (pintype "output"))
    )
    (net (code "97") (name "unconnected-(E11A-QB-Pad9)") (class "Default")
      (node (ref "E11") (pin "9") (pinfunction "QB_9") (pintype "output"))
    )
    (net (code "98") (name "unconnected-(E11A-QC-Pad8)") (class "Default")
      (node (ref "E11") (pin "8") (pinfunction "QC_8") (pintype "output"))
    )
    (net (code "99") (name "unconnected-(E15A-QB-Pad9)") (class "Default")
      (node (ref "E15") (pin "9") (pinfunction "QB_9") (pintype "output"))
    )
    (net (code "100") (name "unconnected-(E15A-QC-Pad8)") (class "Default")
      (node (ref "E15") (pin "8") (pinfunction "QC_8") (pintype "output"))
    )
    (net (code "101") (name "unconnected-(E16A-CLR-Pad2)") (class "Default")
      (node (ref "E16") (pin "2") (pinfunction "CLR_2") (pintype "input"))
    )
    (net (code "102") (name "unconnected-(E16A-PRE-Pad13)") (class "Default")
      (node (ref "E16") (pin "13") (pinfunction "PRE_13") (pintype "input"))
    )
    (net (code "103") (name "unconnected-(E16A-~{Q}-Pad6)") (class "Default")
      (node (ref "E16") (pin "6") (pinfunction "~{Q}_6") (pintype "output"))
    )
    (net (code "104") (name "unconnected-(E17A-CLR-Pad2)") (class "Default")
      (node (ref "E17") (pin "2") (pinfunction "CLR_2") (pintype "input"))
    )
    (net (code "105") (name "unconnected-(E17A-PRE-Pad13)") (class "Default")
      (node (ref "E17") (pin "13") (pinfunction "PRE_13") (pintype "input"))
    )
    (net (code "106") (name "unconnected-(E17A-~{Q}-Pad6)") (class "Default")
      (node (ref "E17") (pin "6") (pinfunction "~{Q}_6") (pintype "output"))
    )
    (net (code "107") (name "unconnected-(E18A-QB-Pad9)") (class "Default")
      (node (ref "E18") (pin "9") (pinfunction "QB_9") (pintype "output"))
    )
    (net (code "108") (name "unconnected-(E18A-QC-Pad8)") (class "Default")
      (node (ref "E18") (pin "8") (pinfunction "QC_8") (pintype "output"))
    )
    (net (code "109") (name "unconnected-(E19A-QB-Pad9)") (class "Default")
      (node (ref "E19") (pin "9") (pinfunction "QB_9") (pintype "output"))
    )
    (net (code "110") (name "unconnected-(E19A-QC-Pad8)") (class "Default")
      (node (ref "E19") (pin "8") (pinfunction "QC_8") (pintype "output"))
    )
    (net (code "111") (name "unconnected-(E20A-QB-Pad9)") (class "Default")
      (node (ref "E20") (pin "9") (pinfunction "QB_9") (pintype "output"))
    )
    (net (code "112") (name "unconnected-(E20A-QC-Pad8)") (class "Default")
      (node (ref "E20") (pin "8") (pinfunction "QC_8") (pintype "output"))
    )
    (net (code "113") (name "unconnected-(E21A-QB-Pad9)") (class "Default")
      (node (ref "E21") (pin "9") (pinfunction "QB_9") (pintype "output"))
    )
    (net (code "114") (name "unconnected-(E21A-QC-Pad8)") (class "Default")
      (node (ref "E21") (pin "8") (pinfunction "QC_8") (pintype "output"))
    )
  )
)
